# M5amigo-RS-485-LTC2877IMSE.net
KiCad netlist of a schematic drawn in EAGLE
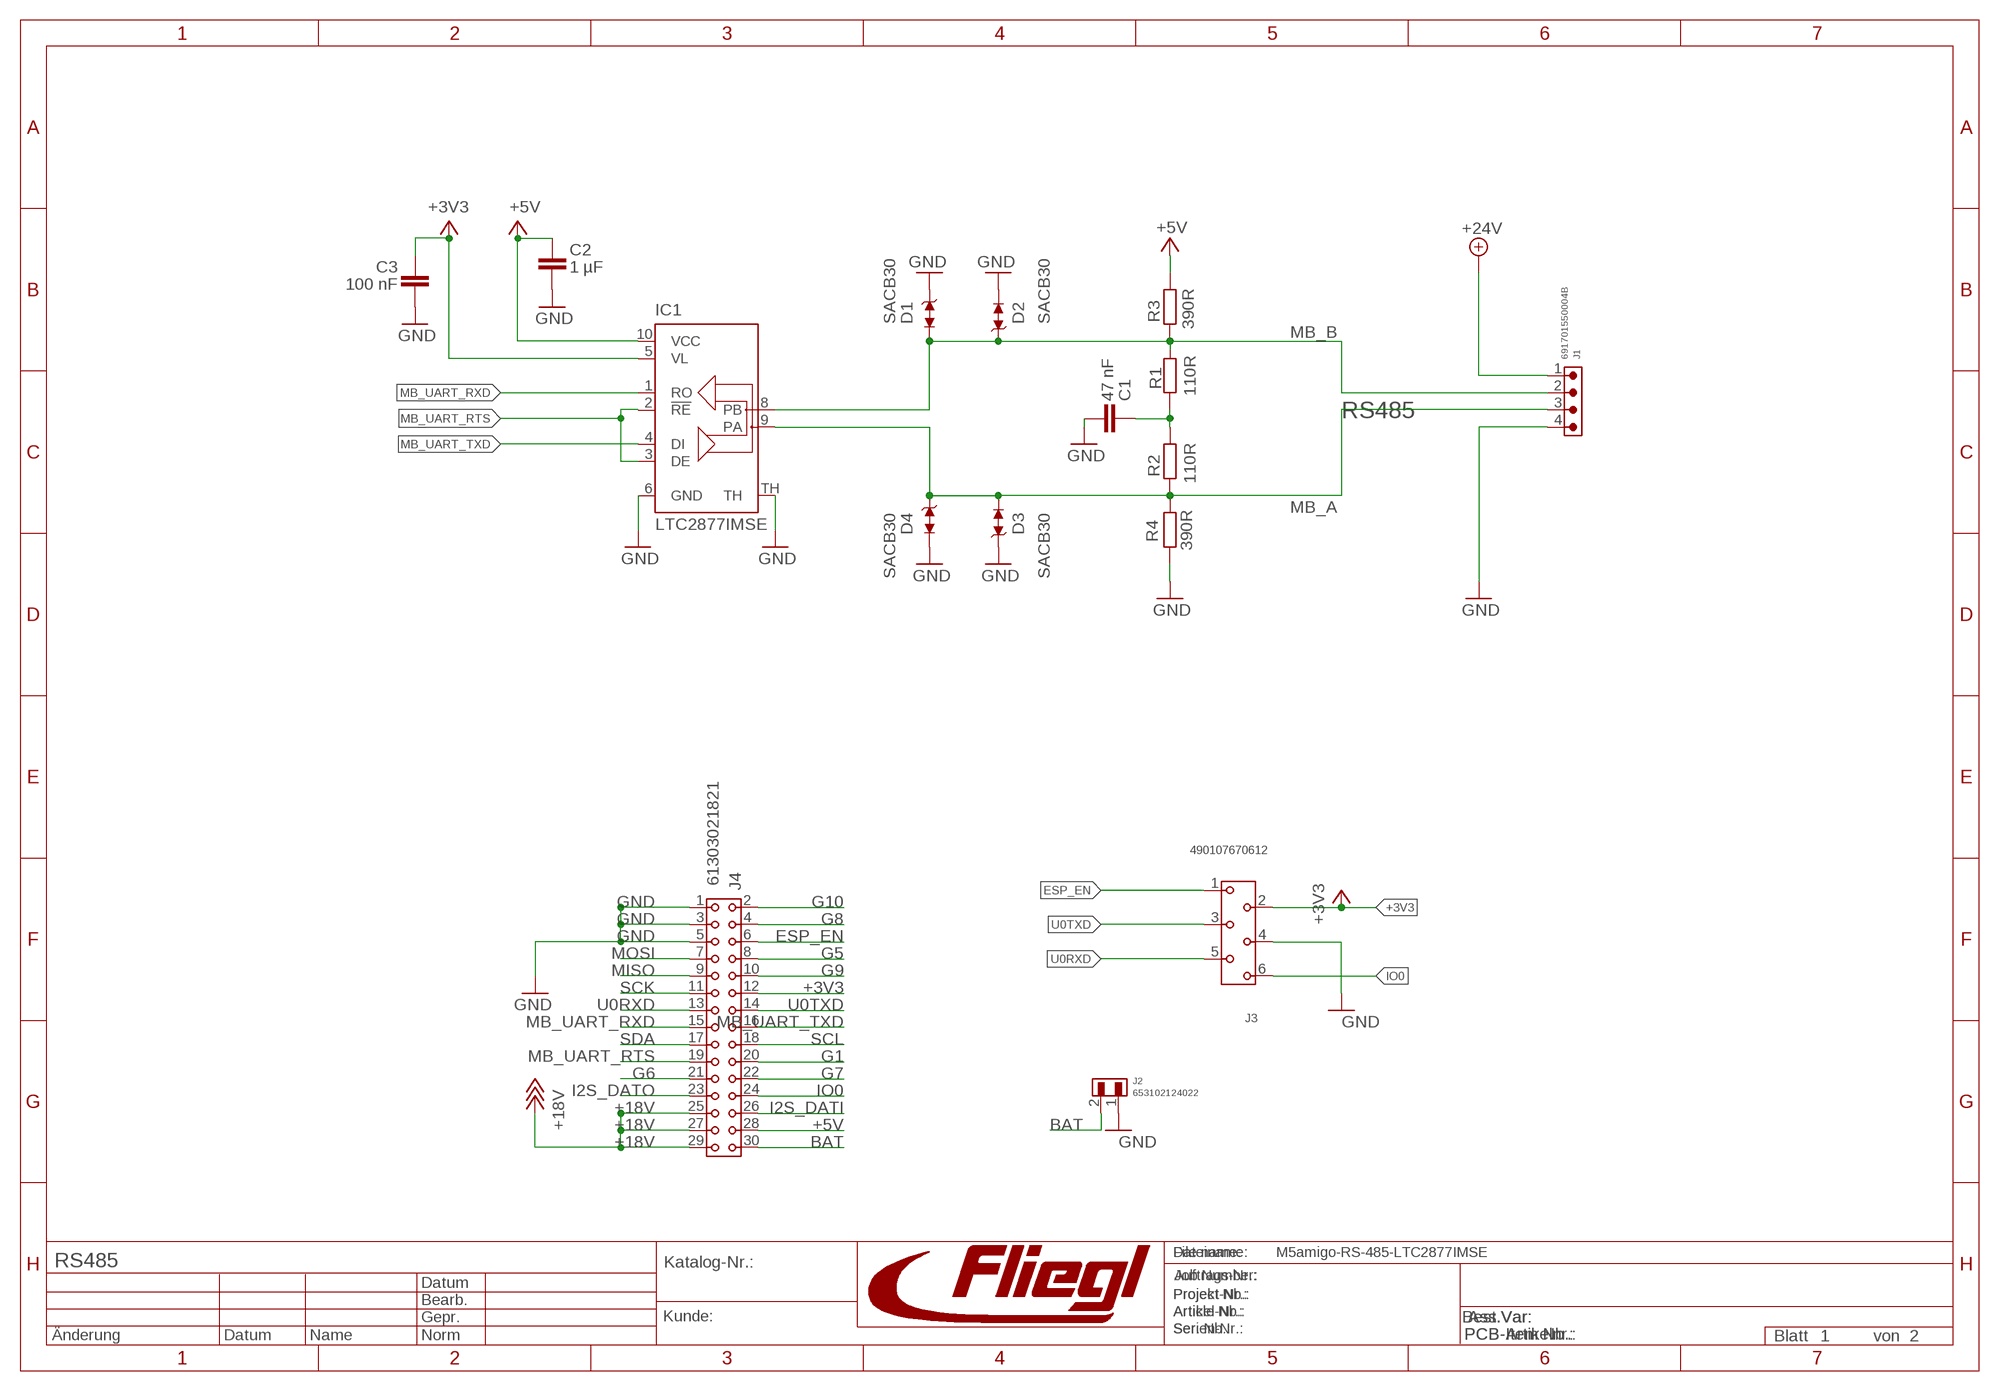
[diagram p0: schematic, sheet 1]
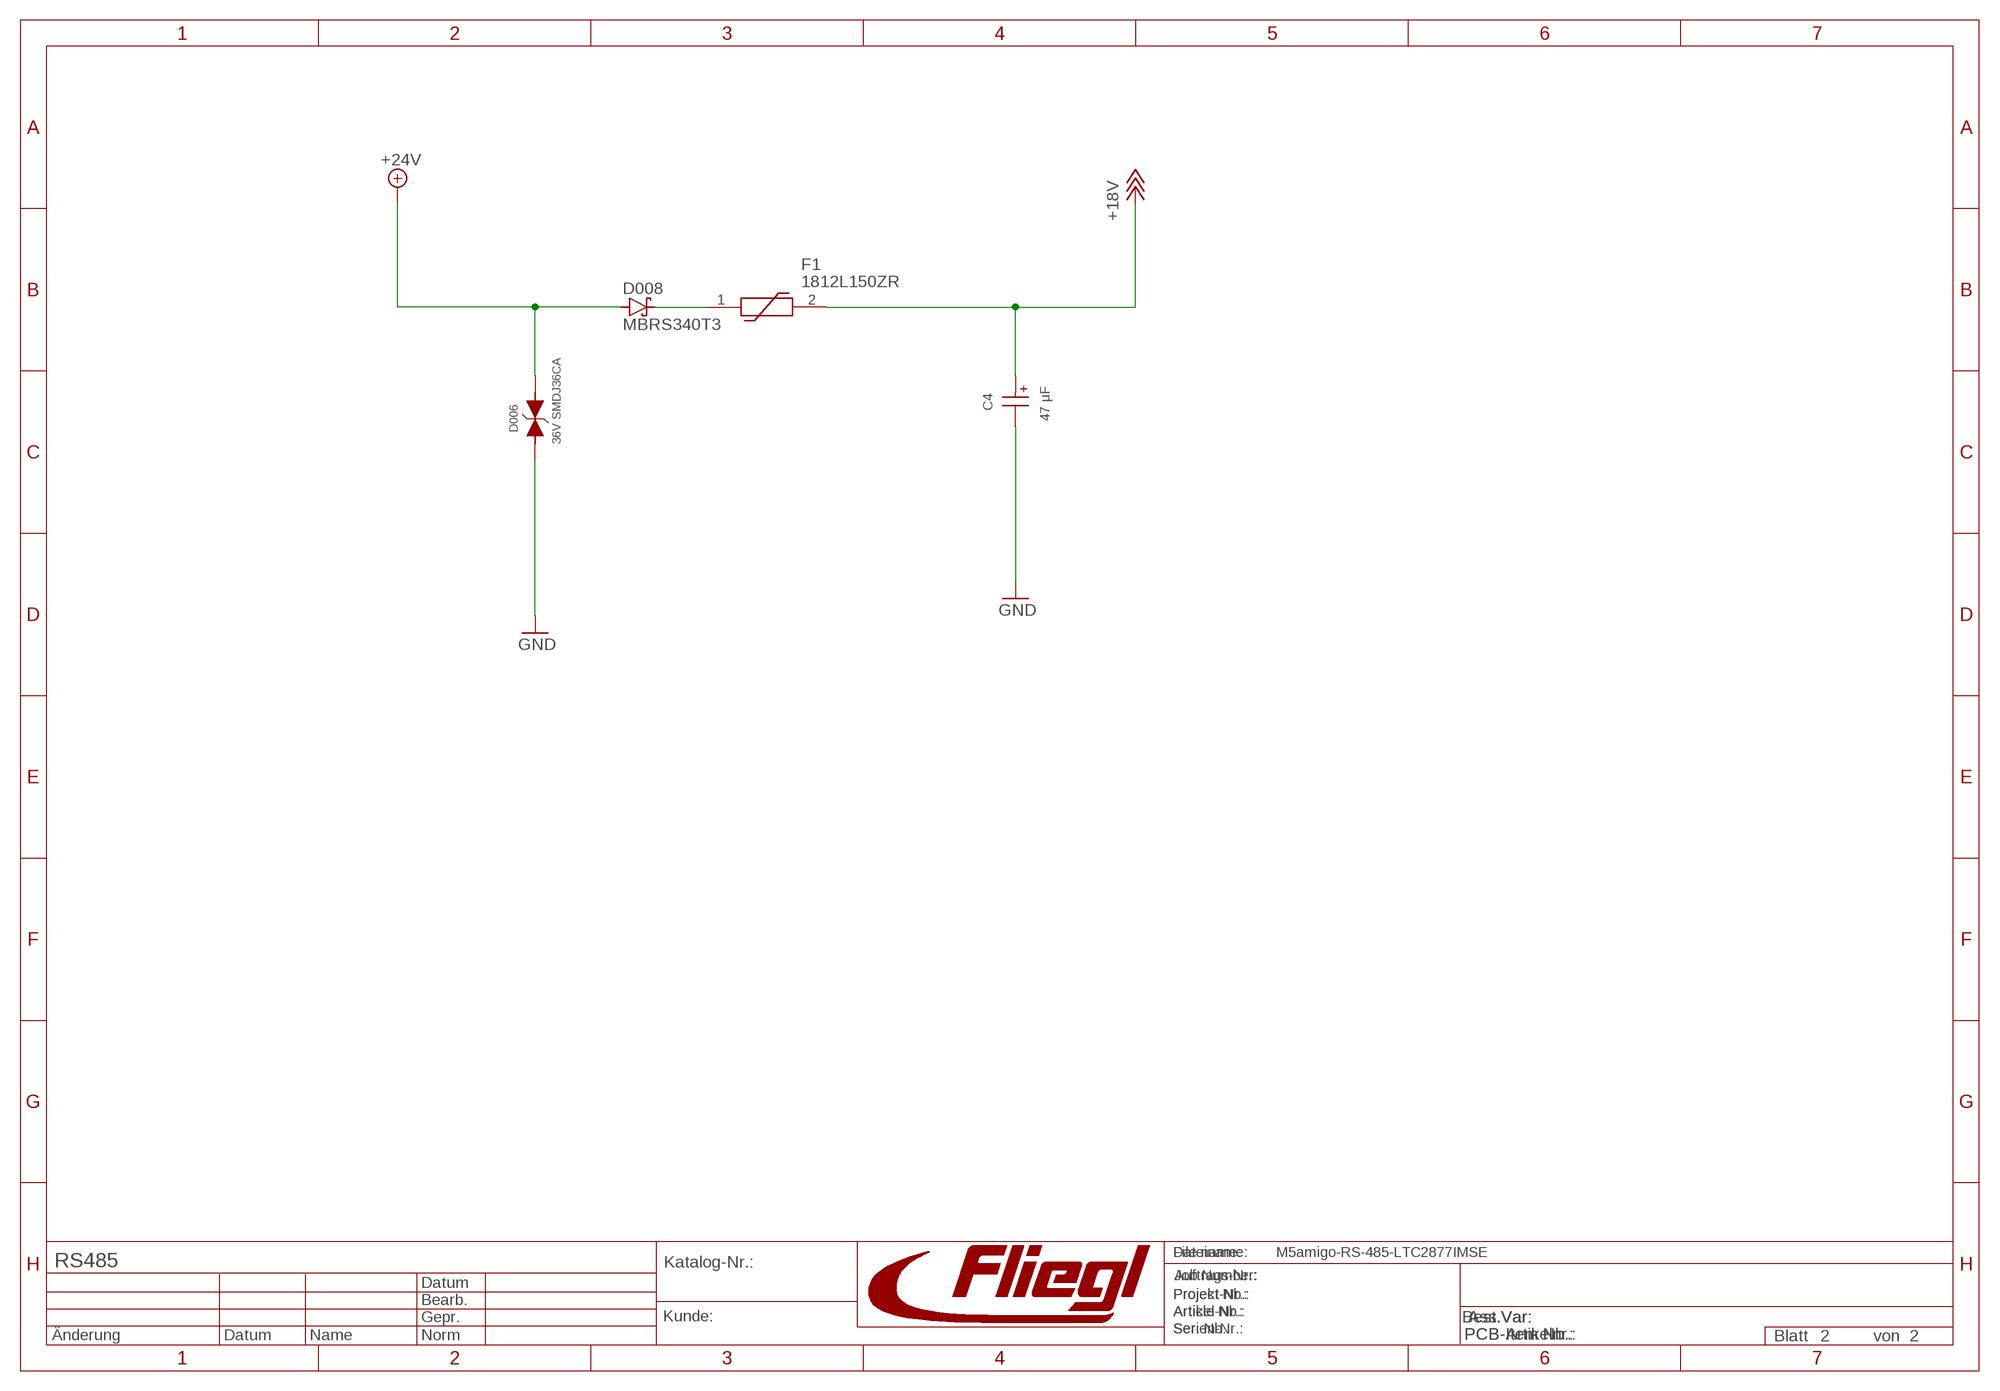
[diagram p1: schematic, sheet 2]

(export (version "E")
  (design (tool "Eeschema 10.0.6"))
  (components
    (comp (ref "C4")
      (value "47 µF")
      (footprint "eagle-import:WCAP-ASLL_6.3X7.7(DXL)")
      (libsource (lib "eagle-import") (part "WCAP-ASLL_6.3X7.7_865060645008"))
    )
    (comp (ref "D006")
      (value "36V SMDJ36CA")
      (footprint "eagle-import:WE-TVSP_DO-214AB_BIDIRECTIONAL")
      (libsource (lib "eagle-import") (part "WE-TVSP_DO-214AB_3000W_BI_824551361"))
    )
    (comp (ref "D008")
      (value "MBRS340T3")
      (footprint "eagle-import:SMC")
      (libsource (lib "eagle-import") (part "MBRS30T34"))
    )
    (comp (ref "F1")
      (value "1812L150ZR")
      (footprint "eagle-import:1812L010DR")
      (fields (field (name "MOUSER_PART_NUMBER") "576-1812L150ZR"))
      (libsource (lib "eagle-import") (part "1812L150ZR"))
    )
    (comp (ref "C1")
      (value "47 nF")
      (footprint "eagle-import:WCAP-CSGP_0402")
      (libsource (lib "eagle-import") (part "WCAP-CSGP_0402_25V(DC)_885012205054"))
    )
    (comp (ref "C2")
      (value "1 µF")
      (footprint "eagle-import:WCAP-CSGP_0402")
      (libsource (lib "eagle-import") (part "WCAP-CSGP_0402_10V(DC)_885012105012"))
    )
    (comp (ref "C3")
      (value "100 nF")
      (footprint "eagle-import:WCAP-CSGP_0402")
      (libsource (lib "eagle-import") (part "WCAP-CSGP_0402_16V(DC)_885012205037"))
    )
    (comp (ref "D1")
      (value "SACB30")
      (footprint "eagle-import:DO214AA")
      (libsource (lib "eagle-import") (part "SACB30"))
    )
    (comp (ref "D2")
      (value "SACB30")
      (footprint "eagle-import:DO214AA")
      (libsource (lib "eagle-import") (part "SACB30"))
    )
    (comp (ref "D3")
      (value "SACB30")
      (footprint "eagle-import:DO214AA")
      (libsource (lib "eagle-import") (part "SACB30"))
    )
    (comp (ref "D4")
      (value "SACB30")
      (footprint "eagle-import:DO214AA")
      (libsource (lib "eagle-import") (part "SACB30"))
    )
    (comp (ref "IC1")
      (value "LTC2877IMSE")
      (footprint "eagle-import:MSOP-10_MSE")
      (libsource (lib "eagle-import") (part "LTC2877IMSE"))
    )
    (comp (ref "J1")
      (value "691701550004B")
      (footprint "eagle-import:691701550004B")
      (libsource (lib "eagle-import") (part "691701550004B"))
    )
    (comp (ref "J2")
      (value "653102124022")
      (footprint "eagle-import:653102124022")
      (libsource (lib "eagle-import") (part "653102124022"))
    )
    (comp (ref "J3")
      (value "490107670612")
      (footprint "eagle-import:490107670612_DEBUGGING")
      (libsource (lib "eagle-import") (part "490107670612_DEBUGGING"))
    )
    (comp (ref "J4")
      (value "61303021821")
      (footprint "eagle-import:61303021821")
      (libsource (lib "eagle-import") (part "6130XX21821_61303021821"))
    )
    (comp (ref "R1")
      (value "110R")
      (footprint "eagle-import:WCAP-CSRF_0402")
      (libsource (lib "eagle-import") (part "R-0402_110R"))
    )
    (comp (ref "R2")
      (value "110R")
      (footprint "eagle-import:WCAP-CSRF_0402")
      (libsource (lib "eagle-import") (part "R-0402_110R"))
    )
    (comp (ref "R3")
      (value "390R")
      (footprint "eagle-import:WCAP-CSMH_0603_R")
      (libsource (lib "eagle-import") (part "R-0603_390R"))
    )
    (comp (ref "R4")
      (value "390R")
      (footprint "eagle-import:WCAP-CSMH_0603_R")
      (libsource (lib "eagle-import") (part "R-0603_390R"))
    )
  )
  (nets
    (net (code "1") (name "+3V3") (class "Default")
      (node (ref "C3") (pin "1") (pinfunction "1_1") (pintype "passive"))
      (node (ref "IC1") (pin "5") (pinfunction "VL_5") (pintype "passive"))
      (node (ref "J3") (pin "2") (pinfunction "2_2") (pintype "passive"))
      (node (ref "J4") (pin "12") (pinfunction "12_12") (pintype "passive"))
    )
    (net (code "2") (name "+5V") (class "Default")
      (node (ref "C2") (pin "1") (pinfunction "1_1") (pintype "passive"))
      (node (ref "IC1") (pin "10") (pinfunction "VCC_10") (pintype "power_in"))
      (node (ref "J4") (pin "28") (pinfunction "28_28") (pintype "passive"))
      (node (ref "R3") (pin "2") (pinfunction "2_2") (pintype "passive"))
    )
    (net (code "3") (name "+18V") (class "Default")
      (node (ref "C4") (pin "1") (pinfunction "+_1") (pintype "passive"))
      (node (ref "F1") (pin "2") (pinfunction "2_2") (pintype "bidirectional"))
      (node (ref "J4") (pin "25") (pinfunction "25_25") (pintype "passive"))
      (node (ref "J4") (pin "27") (pinfunction "27_27") (pintype "passive"))
      (node (ref "J4") (pin "29") (pinfunction "29_29") (pintype "passive"))
    )
    (net (code "4") (name "+24V") (class "Default")
      (node (ref "D006") (pin "2") (pinfunction "2_2") (pintype "passive"))
      (node (ref "D008") (pin "A") (pinfunction "A_A") (pintype "passive"))
      (node (ref "J1") (pin "1") (pinfunction "1_1") (pintype "passive"))
    )
    (net (code "5") (name "BAT") (class "Default")
      (node (ref "J2") (pin "2") (pinfunction "2_2") (pintype "passive"))
      (node (ref "J4") (pin "30") (pinfunction "30_30") (pintype "passive"))
    )
    (net (code "6") (name "ESP_EN") (class "Default")
      (node (ref "J3") (pin "1") (pinfunction "1_1") (pintype "passive"))
      (node (ref "J4") (pin "6") (pinfunction "6_6") (pintype "passive"))
    )
    (net (code "7") (name "G1") (class "Default")
      (node (ref "J4") (pin "20") (pinfunction "20_20") (pintype "passive"))
    )
    (net (code "8") (name "G5") (class "Default")
      (node (ref "J4") (pin "8") (pinfunction "8_8") (pintype "passive"))
    )
    (net (code "9") (name "G6") (class "Default")
      (node (ref "J4") (pin "21") (pinfunction "21_21") (pintype "passive"))
    )
    (net (code "10") (name "G7") (class "Default")
      (node (ref "J4") (pin "22") (pinfunction "22_22") (pintype "passive"))
    )
    (net (code "11") (name "G8") (class "Default")
      (node (ref "J4") (pin "4") (pinfunction "4_4") (pintype "passive"))
    )
    (net (code "12") (name "G9") (class "Default")
      (node (ref "J4") (pin "10") (pinfunction "10_10") (pintype "passive"))
    )
    (net (code "13") (name "G10") (class "Default")
      (node (ref "J4") (pin "2") (pinfunction "2_2") (pintype "passive"))
    )
    (net (code "14") (name "GND") (class "Default")
      (node (ref "C1") (pin "2") (pinfunction "2_2") (pintype "passive"))
      (node (ref "C2") (pin "2") (pinfunction "2_2") (pintype "passive"))
      (node (ref "C3") (pin "2") (pinfunction "2_2") (pintype "passive"))
      (node (ref "C4") (pin "2") (pinfunction "-_2") (pintype "passive"))
      (node (ref "D006") (pin "1") (pinfunction "1_1") (pintype "passive"))
      (node (ref "D1") (pin "C") (pinfunction "K_C") (pintype "passive"))
      (node (ref "D2") (pin "A") (pinfunction "KD_A") (pintype "passive"))
      (node (ref "D3") (pin "C") (pinfunction "K_C") (pintype "passive"))
      (node (ref "D4") (pin "A") (pinfunction "KD_A") (pintype "passive"))
      (node (ref "IC1") (pin "6") (pinfunction "GND_6") (pintype "power_in"))
      (node (ref "IC1") (pin "TH") (pinfunction "TH_TH") (pintype "passive"))
      (node (ref "J1") (pin "4") (pinfunction "4_4") (pintype "passive"))
      (node (ref "J2") (pin "1") (pinfunction "1_1") (pintype "passive"))
      (node (ref "J3") (pin "4") (pinfunction "4_4") (pintype "passive"))
      (node (ref "J4") (pin "1") (pinfunction "1_1") (pintype "passive"))
      (node (ref "J4") (pin "3") (pinfunction "3_3") (pintype "passive"))
      (node (ref "J4") (pin "5") (pinfunction "5_5") (pintype "passive"))
      (node (ref "R4") (pin "1") (pinfunction "1_1") (pintype "passive"))
    )
    (net (code "15") (name "I2S_DATI") (class "Default")
      (node (ref "J4") (pin "26") (pinfunction "26_26") (pintype "passive"))
    )
    (net (code "16") (name "I2S_DATO") (class "Default")
      (node (ref "J4") (pin "23") (pinfunction "23_23") (pintype "passive"))
    )
    (net (code "17") (name "IO0") (class "Default")
      (node (ref "J3") (pin "6") (pinfunction "6_6") (pintype "passive"))
      (node (ref "J4") (pin "24") (pinfunction "24_24") (pintype "passive"))
    )
    (net (code "18") (name "MB_A") (class "Default")
      (node (ref "D3") (pin "A") (pinfunction "KD_A") (pintype "passive"))
      (node (ref "D4") (pin "C") (pinfunction "K_C") (pintype "passive"))
      (node (ref "IC1") (pin "9") (pinfunction "PA_9") (pintype "bidirectional"))
      (node (ref "J1") (pin "3") (pinfunction "3_3") (pintype "passive"))
      (node (ref "R2") (pin "1") (pinfunction "1_1") (pintype "passive"))
      (node (ref "R4") (pin "2") (pinfunction "2_2") (pintype "passive"))
    )
    (net (code "19") (name "MB_B") (class "Default")
      (node (ref "D1") (pin "A") (pinfunction "KD_A") (pintype "passive"))
      (node (ref "D2") (pin "C") (pinfunction "K_C") (pintype "passive"))
      (node (ref "IC1") (pin "8") (pinfunction "PB_8") (pintype "bidirectional"))
      (node (ref "J1") (pin "2") (pinfunction "2_2") (pintype "passive"))
      (node (ref "R1") (pin "2") (pinfunction "2_2") (pintype "passive"))
      (node (ref "R3") (pin "1") (pinfunction "1_1") (pintype "passive"))
    )
    (net (code "20") (name "MB_UART_RTS") (class "Default")
      (node (ref "IC1") (pin "2") (pinfunction "~{RE}_2") (pintype "input"))
      (node (ref "IC1") (pin "3") (pinfunction "DE_3") (pintype "input"))
      (node (ref "J4") (pin "19") (pinfunction "19_19") (pintype "passive"))
    )
    (net (code "21") (name "MB_UART_RXD") (class "Default")
      (node (ref "IC1") (pin "1") (pinfunction "RO_1") (pintype "output"))
      (node (ref "J4") (pin "15") (pinfunction "15_15") (pintype "passive"))
    )
    (net (code "22") (name "MB_UART_TXD") (class "Default")
      (node (ref "IC1") (pin "4") (pinfunction "DI_4") (pintype "input"))
      (node (ref "J4") (pin "16") (pinfunction "16_16") (pintype "passive"))
    )
    (net (code "23") (name "MISO") (class "Default")
      (node (ref "J4") (pin "9") (pinfunction "9_9") (pintype "passive"))
    )
    (net (code "24") (name "MOSI") (class "Default")
      (node (ref "J4") (pin "7") (pinfunction "7_7") (pintype "passive"))
    )
    (net (code "25") (name "Net-(C1-Pad1)") (class "Default")
      (node (ref "C1") (pin "1") (pinfunction "1_1") (pintype "passive"))
      (node (ref "R1") (pin "1") (pinfunction "1_1") (pintype "passive"))
      (node (ref "R2") (pin "2") (pinfunction "2_2") (pintype "passive"))
    )
    (net (code "26") (name "Net-(D008-PadC)") (class "Default")
      (node (ref "D008") (pin "C") (pinfunction "C_C") (pintype "passive"))
      (node (ref "F1") (pin "1") (pinfunction "1_1") (pintype "bidirectional"))
    )
    (net (code "27") (name "SCK") (class "Default")
      (node (ref "J4") (pin "11") (pinfunction "11_11") (pintype "passive"))
    )
    (net (code "28") (name "SCL") (class "Default")
      (node (ref "J4") (pin "18") (pinfunction "18_18") (pintype "passive"))
    )
    (net (code "29") (name "SDA") (class "Default")
      (node (ref "J4") (pin "17") (pinfunction "17_17") (pintype "passive"))
    )
    (net (code "30") (name "U0RXD") (class "Default")
      (node (ref "J3") (pin "5") (pinfunction "5_5") (pintype "passive"))
      (node (ref "J4") (pin "13") (pinfunction "13_13") (pintype "passive"))
    )
    (net (code "31") (name "U0TXD") (class "Default")
      (node (ref "J3") (pin "3") (pinfunction "3_3") (pintype "passive"))
      (node (ref "J4") (pin "14") (pinfunction "14_14") (pintype "passive"))
    )
  )
)
